# Teensy_Intan_Module_JE_T36_v01_20180628.net
KiCad netlist of a schematic drawn in EAGLE
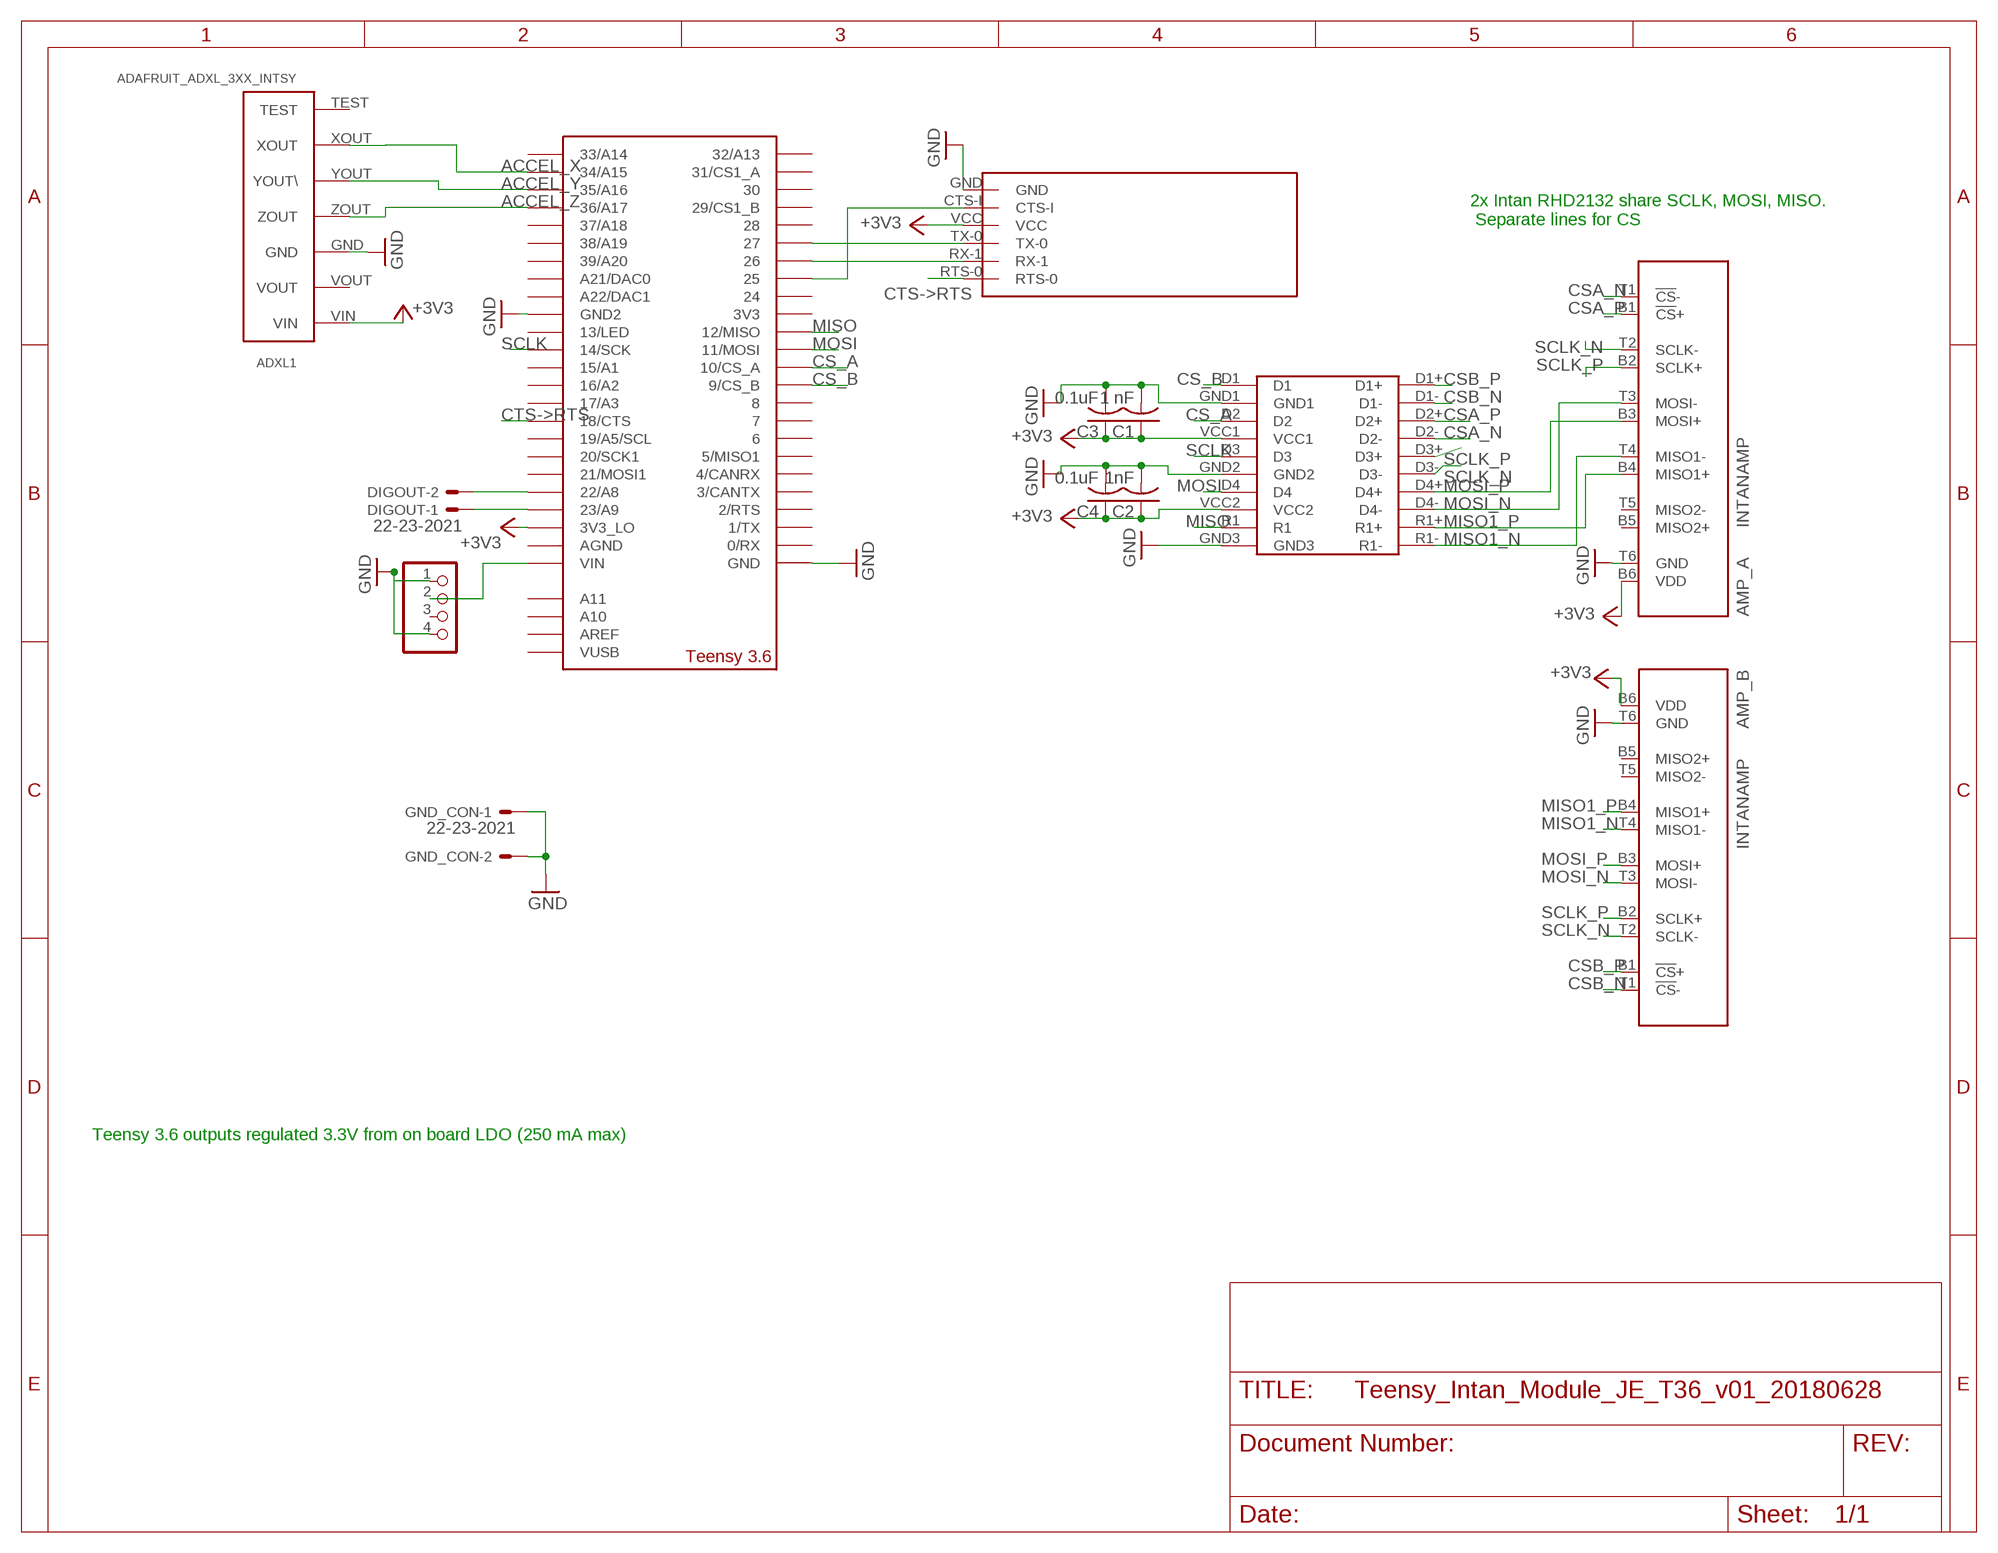
[diagram p0: schematic, sheet 1]

(export (version "E")
  (design (tool "Eeschema 10.0.6"))
  (components
    (comp (ref "ADXL1")
      (value "ADAFRUIT_ADXL_3XX_INTSY")
      (footprint "eagle-import:ADAFRUIT_ADXL_3XX")
      (libsource (lib "eagle-import") (part "ADAFRUIT_ADXL_3XX_INTSY"))
    )
    (comp (ref "AMP_A")
      (value "INTANAMP")
      (footprint "eagle-import:AMPBOARD")
      (libsource (lib "eagle-import") (part "INTANAMP"))
    )
    (comp (ref "AMP_B")
      (value "INTANAMP")
      (footprint "eagle-import:AMPBOARD")
      (libsource (lib "eagle-import") (part "INTANAMP"))
    )
    (comp (ref "C1")
      (value "1 nF")
      (footprint "eagle-import:C025-024X044")
      (libsource (lib "eagle-import") (part "C-US025-024X044"))
    )
    (comp (ref "C2")
      (value "1nF")
      (footprint "eagle-import:C025-024X044")
      (libsource (lib "eagle-import") (part "C-US025-024X044"))
    )
    (comp (ref "C3")
      (value "0.1uF")
      (footprint "eagle-import:C025-024X044")
      (libsource (lib "eagle-import") (part "C-US025-024X044"))
    )
    (comp (ref "C4")
      (value "0.1uF")
      (footprint "eagle-import:C025-024X044")
      (libsource (lib "eagle-import") (part "C-US025-024X044"))
    )
    (comp (ref "DIGOUT")
      (value "22-23-2021")
      (footprint "eagle-import:22-23-2021")
      (fields (field (name "MF") "MOLEX"))
      (libsource (lib "eagle-import") (part "22-23-2021"))
    )
    (comp (ref "GND_CON")
      (value "22-23-2021")
      (footprint "eagle-import:22-23-2021")
      (fields (field (name "MF") "MOLEX"))
      (libsource (lib "eagle-import") (part "22-23-2021"))
    )
    (comp (ref "RN42")
      (value "RN42")
      (footprint "eagle-import:RN42")
      (libsource (lib "eagle-import") (part "RN42"))
    )
    (comp (ref "SW1")
      (value "LiPoIn")
      (footprint "eagle-import:PADS-4")
      (libsource (lib "eagle-import") (part "PADS-4"))
    )
    (comp (ref "U$1")
      (value "SCHMARTBOARD20PIN")
      (footprint "eagle-import:SCHMARTBOARD20PIN")
      (libsource (lib "eagle-import") (part "SCHMARTBOARD20PIN"))
    )
    (comp (ref "U$2")
      (value "TEENSY_3.5/3.6_BASIC")
      (footprint "eagle-import:TEENSY_3.5_3.6_BASIC")
      (libsource (lib "eagle-import") (part "TEENSY_3.5/3.6_BASIC"))
    )
  )
  (nets
    (net (code "1") (name "+3V3") (class "Default")
      (node (ref "ADXL1") (pin "VIN") (pinfunction "VIN_VIN") (pintype "power_in"))
      (node (ref "AMP_A") (pin "B6") (pinfunction "VDD_B6") (pintype "bidirectional"))
      (node (ref "AMP_B") (pin "B6") (pinfunction "VDD_B6") (pintype "bidirectional"))
      (node (ref "C1") (pin "1") (pinfunction "1_1") (pintype "passive"))
      (node (ref "C2") (pin "1") (pinfunction "1_1") (pintype "passive"))
      (node (ref "C3") (pin "1") (pinfunction "1_1") (pintype "passive"))
      (node (ref "C4") (pin "1") (pinfunction "1_1") (pintype "passive"))
      (node (ref "RN42") (pin "VCC") (pinfunction "VCC_VCC") (pintype "bidirectional"))
      (node (ref "U$1") (pin "VCC1") (pinfunction "VCC1_VCC1") (pintype "bidirectional"))
      (node (ref "U$1") (pin "VCC2") (pinfunction "VCC2_VCC2") (pintype "bidirectional"))
      (node (ref "U$2") (pin "3V3_LO") (pinfunction "3V3_LO_3V3_LO") (pintype "bidirectional"))
    )
    (net (code "2") (name "/ACCEL_X") (class "Default")
      (node (ref "ADXL1") (pin "XOUT") (pinfunction "XOUT_XOUT") (pintype "bidirectional"))
      (node (ref "U$2") (pin "34/A15") (pinfunction "34/A15_34/A15") (pintype "input"))
    )
    (net (code "3") (name "/ACCEL_Y") (class "Default")
      (node (ref "ADXL1") (pin "YOUT") (pinfunction "YOUT\\_YOUT") (pintype "bidirectional"))
      (node (ref "U$2") (pin "35/A16") (pinfunction "35/A16_35/A16") (pintype "bidirectional"))
    )
    (net (code "4") (name "/ACCEL_Z") (class "Default")
      (node (ref "ADXL1") (pin "ZOUT") (pinfunction "ZOUT_ZOUT") (pintype "bidirectional"))
      (node (ref "U$2") (pin "36/A17") (pinfunction "36/A17_36/A17") (pintype "bidirectional"))
    )
    (net (code "5") (name "/CSA_N") (class "Default")
      (node (ref "AMP_A") (pin "T1") (pinfunction "~{CS}-_T1") (pintype "bidirectional"))
      (node (ref "U$1") (pin "D2-") (pinfunction "D2-_D2-") (pintype "bidirectional"))
    )
    (net (code "6") (name "/CSA_P") (class "Default")
      (node (ref "AMP_A") (pin "B1") (pinfunction "~{CS}+_B1") (pintype "bidirectional"))
      (node (ref "U$1") (pin "D2+") (pinfunction "D2+_D2+") (pintype "bidirectional"))
    )
    (net (code "7") (name "/CSB_N") (class "Default")
      (node (ref "AMP_B") (pin "T1") (pinfunction "~{CS}-_T1") (pintype "bidirectional"))
      (node (ref "U$1") (pin "D1-") (pinfunction "D1-_D1-") (pintype "bidirectional"))
    )
    (net (code "8") (name "/CSB_P") (class "Default")
      (node (ref "AMP_B") (pin "B1") (pinfunction "~{CS}+_B1") (pintype "bidirectional"))
      (node (ref "U$1") (pin "D1+") (pinfunction "D1+_D1+") (pintype "bidirectional"))
    )
    (net (code "9") (name "/CS_A") (class "Default")
      (node (ref "U$1") (pin "D2") (pinfunction "D2_D2") (pintype "bidirectional"))
      (node (ref "U$2") (pin "10/CS") (pinfunction "10/CS_A_10/CS") (pintype "bidirectional"))
    )
    (net (code "10") (name "/CS_B") (class "Default")
      (node (ref "U$1") (pin "D1") (pinfunction "D1_D1") (pintype "bidirectional"))
      (node (ref "U$2") (pin "9/CS") (pinfunction "9/CS_B_9/CS") (pintype "bidirectional"))
    )
    (net (code "11") (name "/CTS->RTS") (class "Default")
      (node (ref "RN42") (pin "RTS-0") (pinfunction "RTS-0_RTS-0") (pintype "bidirectional"))
      (node (ref "U$2") (pin "18/A4/SDA") (pinfunction "18/CTS_18/A4/SDA") (pintype "bidirectional"))
    )
    (net (code "12") (name "/MISO") (class "Default")
      (node (ref "U$1") (pin "R1") (pinfunction "R1_R1") (pintype "bidirectional"))
      (node (ref "U$2") (pin "12/MISO") (pinfunction "12/MISO_12/MISO") (pintype "bidirectional"))
    )
    (net (code "13") (name "/MISO1_N") (class "Default")
      (node (ref "AMP_A") (pin "T4") (pinfunction "MISO1-_T4") (pintype "bidirectional"))
      (node (ref "AMP_B") (pin "T4") (pinfunction "MISO1-_T4") (pintype "bidirectional"))
      (node (ref "U$1") (pin "R1-") (pinfunction "R1-_R1-") (pintype "bidirectional"))
    )
    (net (code "14") (name "/MISO1_P") (class "Default")
      (node (ref "AMP_A") (pin "B4") (pinfunction "MISO1+_B4") (pintype "bidirectional"))
      (node (ref "AMP_B") (pin "B4") (pinfunction "MISO1+_B4") (pintype "bidirectional"))
      (node (ref "U$1") (pin "R1+") (pinfunction "R1+_R1+") (pintype "bidirectional"))
    )
    (net (code "15") (name "/MOSI") (class "Default")
      (node (ref "U$1") (pin "D4") (pinfunction "D4_D4") (pintype "bidirectional"))
      (node (ref "U$2") (pin "11/MOSI") (pinfunction "11/MOSI_11/MOSI") (pintype "bidirectional"))
    )
    (net (code "16") (name "/MOSI_N") (class "Default")
      (node (ref "AMP_A") (pin "T3") (pinfunction "MOSI-_T3") (pintype "bidirectional"))
      (node (ref "AMP_B") (pin "T3") (pinfunction "MOSI-_T3") (pintype "bidirectional"))
      (node (ref "U$1") (pin "D4-") (pinfunction "D4-_D4-") (pintype "bidirectional"))
    )
    (net (code "17") (name "/MOSI_P") (class "Default")
      (node (ref "AMP_A") (pin "B3") (pinfunction "MOSI+_B3") (pintype "bidirectional"))
      (node (ref "AMP_B") (pin "B3") (pinfunction "MOSI+_B3") (pintype "bidirectional"))
      (node (ref "U$1") (pin "D4+") (pinfunction "D4+_D4+") (pintype "bidirectional"))
    )
    (net (code "18") (name "/SCLK") (class "Default")
      (node (ref "U$1") (pin "D3") (pinfunction "D3_D3") (pintype "bidirectional"))
      (node (ref "U$2") (pin "14/A0") (pinfunction "14/SCK_14/A0") (pintype "bidirectional"))
    )
    (net (code "19") (name "/SCLK_N") (class "Default")
      (node (ref "AMP_A") (pin "T2") (pinfunction "SCLK-_T2") (pintype "bidirectional"))
      (node (ref "AMP_B") (pin "T2") (pinfunction "SCLK-_T2") (pintype "bidirectional"))
      (node (ref "U$1") (pin "D3-") (pinfunction "D3-_D3-") (pintype "bidirectional"))
    )
    (net (code "20") (name "/SCLK_P") (class "Default")
      (node (ref "AMP_A") (pin "B2") (pinfunction "SCLK+_B2") (pintype "bidirectional"))
      (node (ref "AMP_B") (pin "B2") (pinfunction "SCLK+_B2") (pintype "bidirectional"))
      (node (ref "U$1") (pin "D3+") (pinfunction "D3+_D3+") (pintype "bidirectional"))
    )
    (net (code "21") (name "GND") (class "Default")
      (node (ref "ADXL1") (pin "GND") (pinfunction "GND_GND") (pintype "power_in"))
      (node (ref "AMP_A") (pin "T6") (pinfunction "GND_T6") (pintype "power_in"))
      (node (ref "AMP_B") (pin "T6") (pinfunction "GND_T6") (pintype "power_in"))
      (node (ref "C1") (pin "2") (pinfunction "2_2") (pintype "passive"))
      (node (ref "C2") (pin "2") (pinfunction "2_2") (pintype "passive"))
      (node (ref "C3") (pin "2") (pinfunction "2_2") (pintype "passive"))
      (node (ref "C4") (pin "2") (pinfunction "2_2") (pintype "passive"))
      (node (ref "GND_CON") (pin "1") (pinfunction "S_1") (pintype "passive"))
      (node (ref "GND_CON") (pin "2") (pinfunction "S_2") (pintype "passive"))
      (node (ref "RN42") (pin "GND") (pinfunction "GND_GND") (pintype "bidirectional"))
      (node (ref "SW1") (pin "1") (pinfunction "1_1") (pintype "passive"))
      (node (ref "SW1") (pin "4") (pinfunction "4_4") (pintype "passive"))
      (node (ref "U$1") (pin "GND1") (pinfunction "GND1_GND1") (pintype "bidirectional"))
      (node (ref "U$1") (pin "GND2") (pinfunction "GND2_GND2") (pintype "bidirectional"))
      (node (ref "U$1") (pin "GND3") (pinfunction "GND3_GND3") (pintype "bidirectional"))
      (node (ref "U$2") (pin "GND") (pinfunction "GND_GND") (pintype "bidirectional"))
      (node (ref "U$2") (pin "GND2") (pinfunction "GND2_GND2") (pintype "bidirectional"))
    )
    (net (code "22") (name "Net-(DIGOUTA-S)") (class "Default")
      (node (ref "DIGOUT") (pin "1") (pinfunction "S_1") (pintype "passive"))
      (node (ref "U$2") (pin "23/A9") (pinfunction "23/A9_23/A9") (pintype "bidirectional"))
    )
    (net (code "23") (name "Net-(DIGOUTB-S)") (class "Default")
      (node (ref "DIGOUT") (pin "2") (pinfunction "S_2") (pintype "passive"))
      (node (ref "U$2") (pin "22/A8") (pinfunction "22/A8_22/A8") (pintype "bidirectional"))
    )
    (net (code "24") (name "Net-(RN42-PadCTS-I)") (class "Default")
      (node (ref "RN42") (pin "CTS-I") (pinfunction "CTS-I_CTS-I") (pintype "bidirectional"))
      (node (ref "U$2") (pin "25") (pinfunction "25_25") (pintype "bidirectional"))
    )
    (net (code "25") (name "Net-(RN42-PadRX-1)") (class "Default")
      (node (ref "RN42") (pin "RX-1") (pinfunction "RX-1_RX-1") (pintype "bidirectional"))
      (node (ref "U$2") (pin "26") (pinfunction "26_26") (pintype "bidirectional"))
    )
    (net (code "26") (name "Net-(RN42-PadTX-0)") (class "Default")
      (node (ref "RN42") (pin "TX-0") (pinfunction "TX-0_TX-0") (pintype "bidirectional"))
      (node (ref "U$2") (pin "27") (pinfunction "27_27") (pintype "bidirectional"))
    )
    (net (code "27") (name "Net-(SW1-Pad2)") (class "Default")
      (node (ref "SW1") (pin "2") (pinfunction "2_2") (pintype "passive"))
      (node (ref "U$2") (pin "VIN") (pinfunction "VIN_VIN") (pintype "bidirectional"))
    )
    (net (code "28") (name "unconnected-(ADXL1-PadTEST)") (class "Default")
      (node (ref "ADXL1") (pin "TEST") (pinfunction "TEST_TEST") (pintype "no_connect"))
    )
    (net (code "29") (name "unconnected-(ADXL1-PadVOUT)") (class "Default")
      (node (ref "ADXL1") (pin "VOUT") (pinfunction "VOUT_VOUT") (pintype "bidirectional"))
    )
    (net (code "30") (name "unconnected-(AMP_A-MISO2+-PadB5)") (class "Default")
      (node (ref "AMP_A") (pin "B5") (pinfunction "MISO2+_B5") (pintype "bidirectional"))
    )
    (net (code "31") (name "unconnected-(AMP_A-MISO2--PadT5)") (class "Default")
      (node (ref "AMP_A") (pin "T5") (pinfunction "MISO2-_T5") (pintype "bidirectional"))
    )
    (net (code "32") (name "unconnected-(AMP_B-MISO2+-PadB5)") (class "Default")
      (node (ref "AMP_B") (pin "B5") (pinfunction "MISO2+_B5") (pintype "bidirectional"))
    )
    (net (code "33") (name "unconnected-(AMP_B-MISO2--PadT5)") (class "Default")
      (node (ref "AMP_B") (pin "T5") (pinfunction "MISO2-_T5") (pintype "bidirectional"))
    )
    (net (code "34") (name "unconnected-(SW1-Pad3)") (class "Default")
      (node (ref "SW1") (pin "3") (pinfunction "3_3") (pintype "passive"))
    )
    (net (code "35") (name "unconnected-(U$2-2{slash}RTS-Pad2)") (class "Default")
      (node (ref "U$2") (pin "2") (pinfunction "2/RTS_2") (pintype "bidirectional"))
    )
    (net (code "36") (name "unconnected-(U$2-5{slash}MISO1-Pad5)") (class "Default")
      (node (ref "U$2") (pin "5") (pinfunction "5/MISO1_5") (pintype "bidirectional"))
    )
    (net (code "37") (name "unconnected-(U$2-13{slash}LED-Pad13{slash}SCK)") (class "Default")
      (node (ref "U$2") (pin "13/SCK") (pinfunction "13/LED_13/SCK") (pintype "bidirectional"))
    )
    (net (code "38") (name "unconnected-(U$2-20{slash}SCK1-Pad20{slash}A6)") (class "Default")
      (node (ref "U$2") (pin "20/A6") (pinfunction "20/SCK1_20/A6") (pintype "bidirectional"))
    )
    (net (code "39") (name "unconnected-(U$2-21{slash}MOSI1-Pad21{slash}A7)") (class "Default")
      (node (ref "U$2") (pin "21/A7") (pinfunction "21/MOSI1_21/A7") (pintype "bidirectional"))
    )
    (net (code "40") (name "unconnected-(U$2-29{slash}CS1_B-Pad29)") (class "Default")
      (node (ref "U$2") (pin "29") (pinfunction "29/CS1_B_29") (pintype "bidirectional"))
    )
    (net (code "41") (name "unconnected-(U$2-31{slash}CS1_A-Pad31{slash}A12)") (class "Default")
      (node (ref "U$2") (pin "31/A12") (pinfunction "31/CS1_A_31/A12") (pintype "bidirectional"))
    )
    (net (code "42") (name "unconnected-(U$2-A21{slash}DAC0-Pad21{slash}DAC0)") (class "Default")
      (node (ref "U$2") (pin "21/DAC0") (pinfunction "A21/DAC0_21/DAC0") (pintype "bidirectional"))
    )
    (net (code "43") (name "unconnected-(U$2-Pad0{slash}RX)") (class "Default")
      (node (ref "U$2") (pin "0/RX") (pinfunction "0/RX_0/RX") (pintype "bidirectional"))
    )
    (net (code "44") (name "unconnected-(U$2-Pad1{slash}TX)") (class "Default")
      (node (ref "U$2") (pin "1/TX") (pinfunction "1/TX_1/TX") (pintype "bidirectional"))
    )
    (net (code "45") (name "unconnected-(U$2-Pad3V3)") (class "Default")
      (node (ref "U$2") (pin "3V3") (pinfunction "3V3_3V3") (pintype "bidirectional"))
    )
    (net (code "46") (name "unconnected-(U$2-Pad3{slash}CANTX)") (class "Default")
      (node (ref "U$2") (pin "3/CANTX") (pinfunction "3/CANTX_3/CANTX") (pintype "bidirectional"))
    )
    (net (code "47") (name "unconnected-(U$2-Pad4{slash}CANRX)") (class "Default")
      (node (ref "U$2") (pin "4/CANRX") (pinfunction "4/CANRX_4/CANRX") (pintype "bidirectional"))
    )
    (net (code "48") (name "unconnected-(U$2-Pad6)") (class "Default")
      (node (ref "U$2") (pin "6") (pinfunction "6_6") (pintype "bidirectional"))
    )
    (net (code "49") (name "unconnected-(U$2-Pad7)") (class "Default")
      (node (ref "U$2") (pin "7") (pinfunction "7_7") (pintype "bidirectional"))
    )
    (net (code "50") (name "unconnected-(U$2-Pad8)") (class "Default")
      (node (ref "U$2") (pin "8") (pinfunction "8_8") (pintype "bidirectional"))
    )
    (net (code "51") (name "unconnected-(U$2-Pad15{slash}A1)") (class "Default")
      (node (ref "U$2") (pin "15/A1") (pinfunction "15/A1_15/A1") (pintype "bidirectional"))
    )
    (net (code "52") (name "unconnected-(U$2-Pad16{slash}A2)") (class "Default")
      (node (ref "U$2") (pin "16/A2") (pinfunction "16/A2_16/A2") (pintype "bidirectional"))
    )
    (net (code "53") (name "unconnected-(U$2-Pad17{slash}A3)") (class "Default")
      (node (ref "U$2") (pin "17/A3") (pinfunction "17/A3_17/A3") (pintype "bidirectional"))
    )
    (net (code "54") (name "unconnected-(U$2-Pad19{slash}A5{slash}SCL)") (class "Default")
      (node (ref "U$2") (pin "19/A5/SCL") (pinfunction "19/A5/SCL_19/A5/SCL") (pintype "bidirectional"))
    )
    (net (code "55") (name "unconnected-(U$2-Pad24)") (class "Default")
      (node (ref "U$2") (pin "24") (pinfunction "24_24") (pintype "bidirectional"))
    )
    (net (code "56") (name "unconnected-(U$2-Pad28)") (class "Default")
      (node (ref "U$2") (pin "28") (pinfunction "28_28") (pintype "bidirectional"))
    )
    (net (code "57") (name "unconnected-(U$2-Pad30)") (class "Default")
      (node (ref "U$2") (pin "30") (pinfunction "30_30") (pintype "bidirectional"))
    )
    (net (code "58") (name "unconnected-(U$2-Pad32{slash}A13)") (class "Default")
      (node (ref "U$2") (pin "32/A13") (pinfunction "32/A13_32/A13") (pintype "bidirectional"))
    )
    (net (code "59") (name "unconnected-(U$2-Pad33{slash}A14)") (class "Default")
      (node (ref "U$2") (pin "33/A14") (pinfunction "33/A14_33/A14") (pintype "bidirectional"))
    )
    (net (code "60") (name "unconnected-(U$2-Pad37{slash}A18)") (class "Default")
      (node (ref "U$2") (pin "37/A18") (pinfunction "37/A18_37/A18") (pintype "bidirectional"))
    )
    (net (code "61") (name "unconnected-(U$2-Pad38{slash}A19)") (class "Default")
      (node (ref "U$2") (pin "38/A19") (pinfunction "38/A19_38/A19") (pintype "bidirectional"))
    )
    (net (code "62") (name "unconnected-(U$2-Pad39{slash}A20)") (class "Default")
      (node (ref "U$2") (pin "39/A20") (pinfunction "39/A20_39/A20") (pintype "bidirectional"))
    )
    (net (code "63") (name "unconnected-(U$2-PadA10)") (class "Default")
      (node (ref "U$2") (pin "A10") (pinfunction "A10_A10") (pintype "bidirectional"))
    )
    (net (code "64") (name "unconnected-(U$2-PadA11)") (class "Default")
      (node (ref "U$2") (pin "A11") (pinfunction "A11_A11") (pintype "bidirectional"))
    )
    (net (code "65") (name "unconnected-(U$2-PadA22{slash}DAC1)") (class "Default")
      (node (ref "U$2") (pin "A22/DAC1") (pinfunction "A22/DAC1_A22/DAC1") (pintype "bidirectional"))
    )
    (net (code "66") (name "unconnected-(U$2-PadAGND)") (class "Default")
      (node (ref "U$2") (pin "AGND") (pinfunction "AGND_AGND") (pintype "bidirectional"))
    )
    (net (code "67") (name "unconnected-(U$2-PadAREF)") (class "Default")
      (node (ref "U$2") (pin "AREF") (pinfunction "AREF_AREF") (pintype "bidirectional"))
    )
    (net (code "68") (name "unconnected-(U$2-PadVUSB)") (class "Default")
      (node (ref "U$2") (pin "VUSB") (pinfunction "VUSB_VUSB") (pintype "bidirectional"))
    )
  )
)
